# EVK-IRIS-W1-SRAM_RESET_STRAPING.net
KiCad netlist of a schematic drawn in Altium Designer
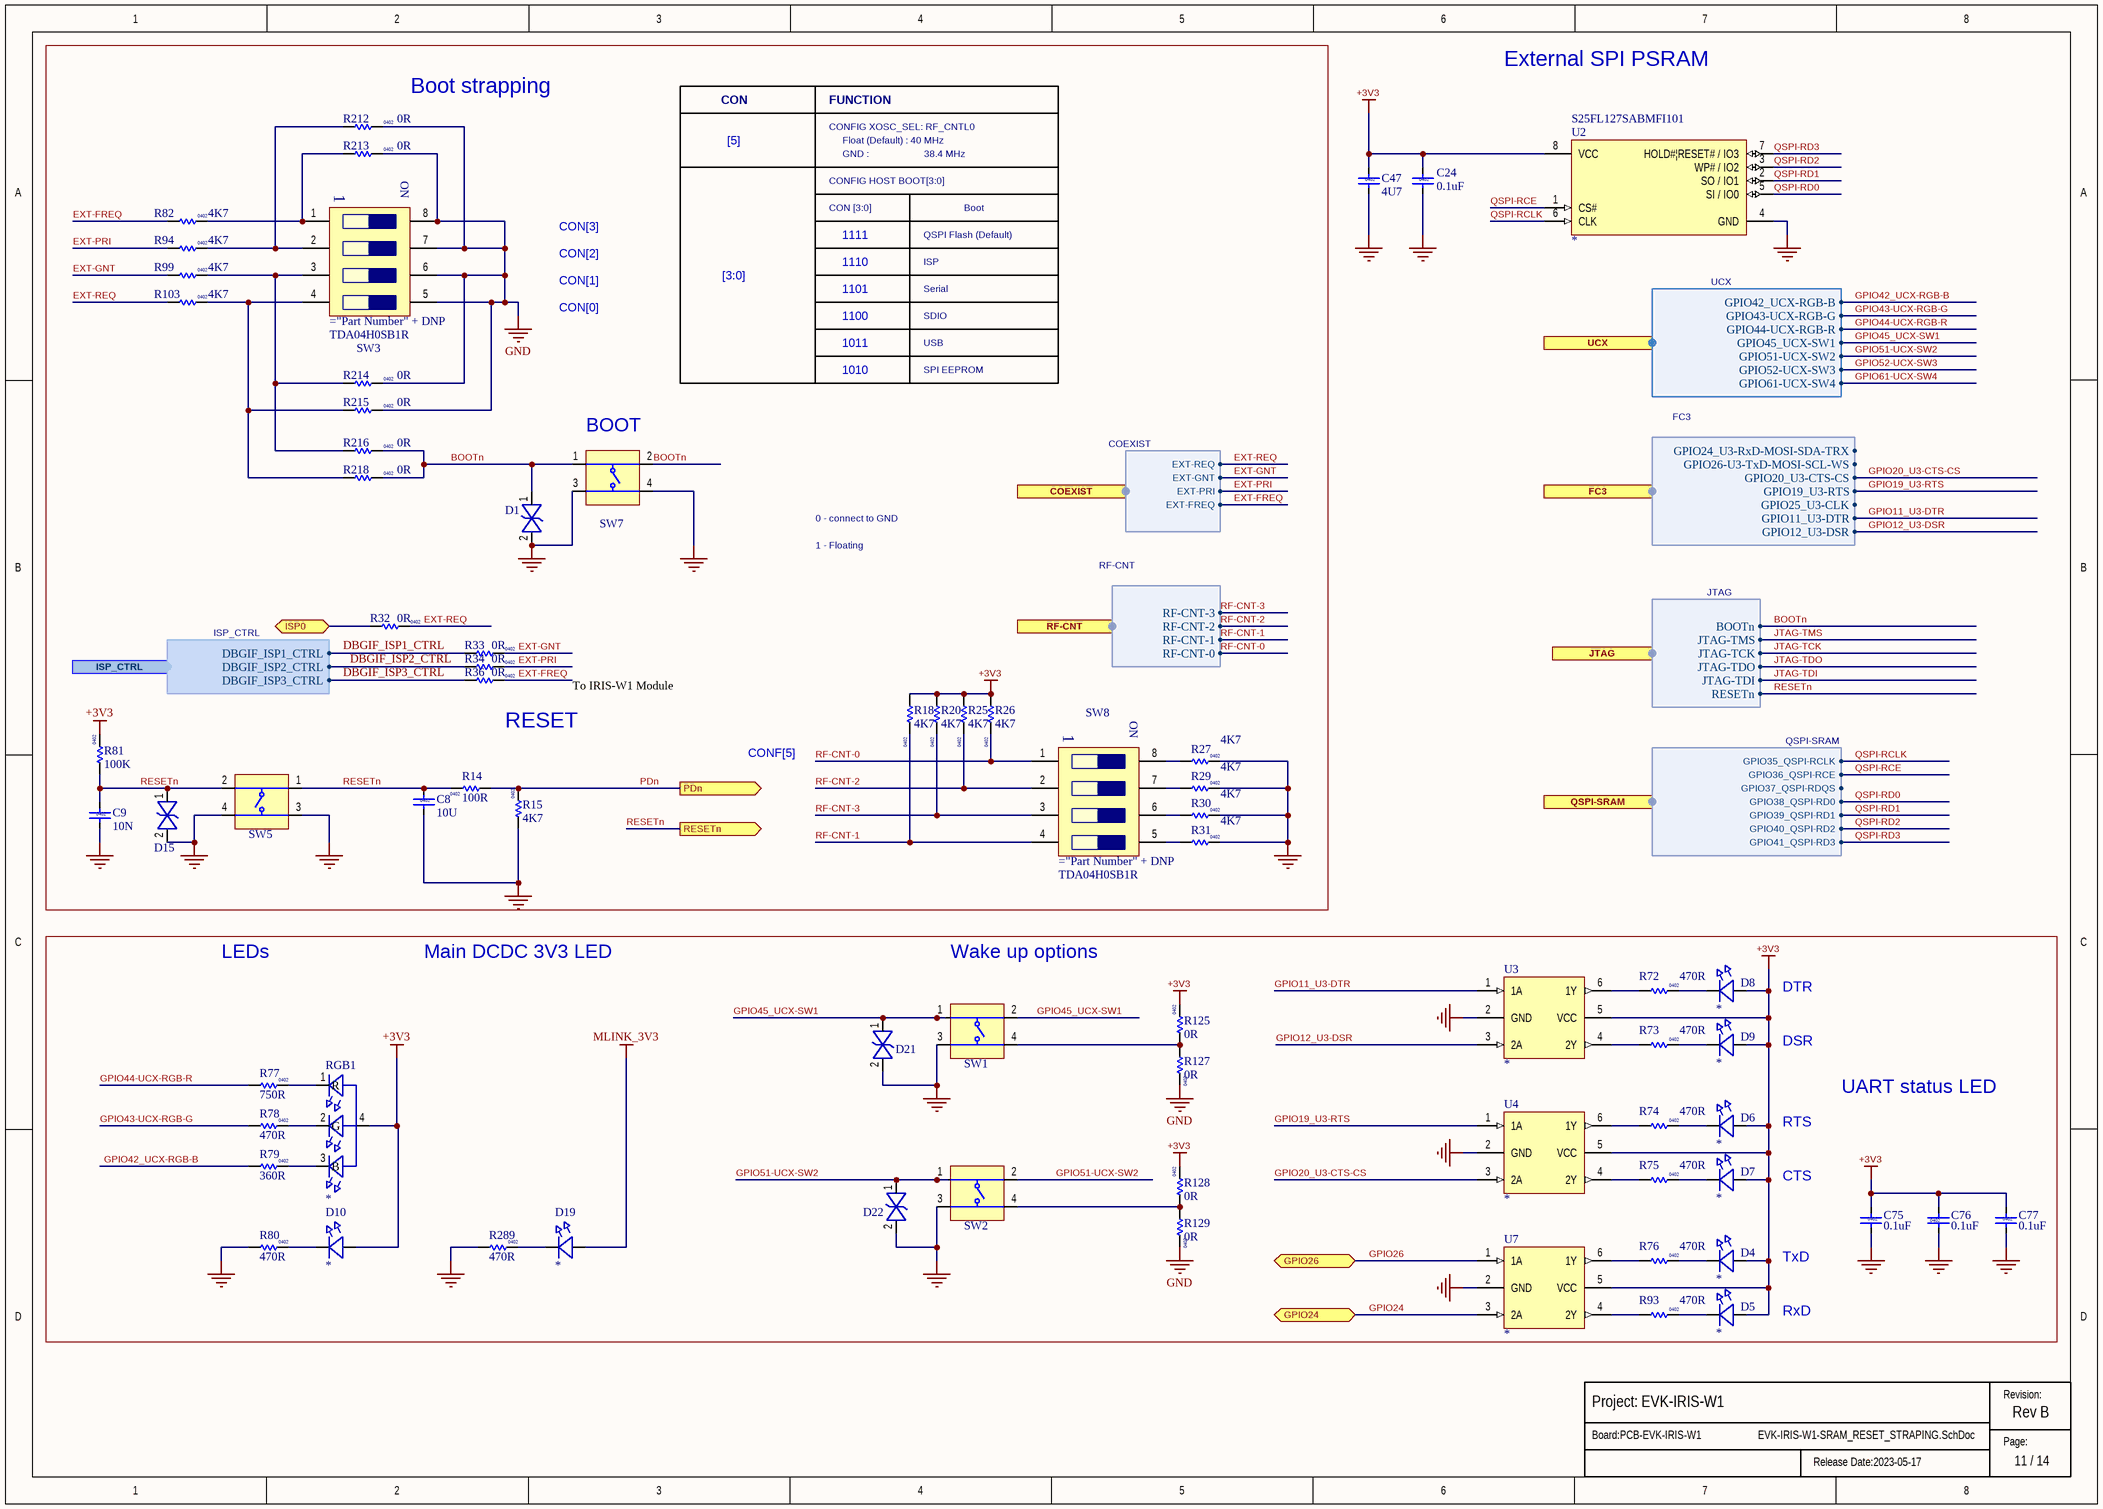
[diagram p0: EVK-IRIS-W1-SRAM_RESET_STRAPING.SchDoc]

(export (version "E")
  (design (tool "Eeschema 10.0.6"))
  (components
    (comp (ref "C8")
      (value "10U")
      (footprint "Cap 0402 HD")
      (description "CAP CER X5R 0402 10U 20% 10V")
      (fields
        (field (name "SIZE") "0402")
        (field (name "PART NUMBER") "UBXH01-0000244")
        (field (name "TOLERANCE") "20%")
        (field (name "EDITOR") "dario.antonaz")
        (field (name "RELEASED BY") "jure.podmenik")
      )
      (libsource (lib "UBX_Parts_DB_Lib") (part "Cap Chip"))
    )
    (comp (ref "C9")
      (value "10N")
      (footprint "Cap 0402")
      (description "CAP CER X7R 0402 10N 10% 16V")
      (fields
        (field (name "SIZE") "0402")
        (field (name "PART NUMBER") "UBXH01-0023025")
        (field (name "TOLERANCE") "10%")
        (field (name "EDITOR") "roland.rust")
        (field (name "RELEASED BY") "anthony.gergis")
      )
      (libsource (lib "UBX_Parts_DB_Lib") (part "Cap Chip"))
    )
    (comp (ref "C24")
      (value "0.1uF")
      (footprint "Cap 0402 HD")
      (description "Cap, Ceramic 0.1uF 10V 10% X5R 0402")
      (fields
        (field (name "SIZE") "0402")
        (field (name "PART NUMBER") "120-00016")
        (field (name "TOLERANCE") "+/- 10%")
      )
      (libsource (lib "Arena_Parts_DB_Lib") (part "Cap Chip"))
    )
    (comp (ref "C47")
      (value "4U7")
      (footprint "Cap 0402 HD")
      (description "CAP CER X5R 0402 4U7 20% 10V")
      (fields
        (field (name "SIZE") "0402")
        (field (name "PART NUMBER") "UBXH01-0000243")
        (field (name "TOLERANCE") "20%")
        (field (name "EDITOR") "martin.pilik")
        (field (name "RELEASED BY") "fabrice.bret-dibat")
      )
      (libsource (lib "UBX_Parts_DB_Lib") (part "Cap Chip"))
    )
    (comp (ref "C75")
      (value "0.1uF")
      (footprint "Cap 0402 HD")
      (description "Cap, Ceramic 0.1uF 10V 10% X5R 0402")
      (fields
        (field (name "SIZE") "0402")
        (field (name "PART NUMBER") "120-00016")
        (field (name "TOLERANCE") "+/- 10%")
      )
      (libsource (lib "Arena_Parts_DB_Lib") (part "Cap Chip"))
    )
    (comp (ref "C76")
      (value "0.1uF")
      (footprint "Cap 0402 HD")
      (description "Cap, Ceramic 0.1uF 10V 10% X5R 0402")
      (fields
        (field (name "SIZE") "0402")
        (field (name "PART NUMBER") "120-00016")
        (field (name "TOLERANCE") "+/- 10%")
      )
      (libsource (lib "Arena_Parts_DB_Lib") (part "Cap Chip"))
    )
    (comp (ref "C77")
      (value "0.1uF")
      (footprint "Cap 0402 HD")
      (description "Cap, Ceramic 0.1uF 10V 10% X5R 0402")
      (fields
        (field (name "SIZE") "0402")
        (field (name "PART NUMBER") "120-00016")
        (field (name "TOLERANCE") "+/- 10%")
      )
      (libsource (lib "Arena_Parts_DB_Lib") (part "Cap Chip"))
    )
    (comp (ref "D1")
      (value "110-00019")
      (footprint "SOD-923")
      (description "Diode, ESD9B, 3.3V, ST5G, SOD-923")
      (fields (field (name "VOLTAGE") "3.3V"))
      (libsource (lib "Arena_Parts_DB_Lib") (part "Diode_TVS"))
    )
    (comp (ref "D4")
      (value "UBXH11-0000018")
      (footprint "LED-0603")
      (description "LED CHIP 0603 LOW CURRENT OSRAM 0.002A GREEN 2.2V 2mA")
      (fields
        (field (name "COLOR") "*")
        (field (name "MANUFACTURER") "Osram")
        (field (name "EDITOR") "johann.furrer")
        (field (name "RELEASED BY") "martin.grasse")
      )
      (libsource (lib "UBX_Parts_DB_Lib") (part "LED_BASE"))
    )
    (comp (ref "D5")
      (value "UBXH11-0000018")
      (footprint "LED-0603")
      (description "LED CHIP 0603 LOW CURRENT OSRAM 0.002A GREEN 2.2V 2mA")
      (fields
        (field (name "COLOR") "*")
        (field (name "MANUFACTURER") "Osram")
        (field (name "EDITOR") "johann.furrer")
        (field (name "RELEASED BY") "martin.grasse")
      )
      (libsource (lib "UBX_Parts_DB_Lib") (part "LED_BASE"))
    )
    (comp (ref "D6")
      (value "UBXH11-0000018")
      (footprint "LED-0603")
      (description "LED CHIP 0603 LOW CURRENT OSRAM 0.002A GREEN 2.2V 2mA")
      (fields
        (field (name "COLOR") "*")
        (field (name "MANUFACTURER") "Osram")
        (field (name "EDITOR") "johann.furrer")
        (field (name "RELEASED BY") "martin.grasse")
      )
      (libsource (lib "UBX_Parts_DB_Lib") (part "LED_BASE"))
    )
    (comp (ref "D7")
      (value "UBXH11-0000018")
      (footprint "LED-0603")
      (description "LED CHIP 0603 LOW CURRENT OSRAM 0.002A GREEN 2.2V 2mA")
      (fields
        (field (name "COLOR") "*")
        (field (name "MANUFACTURER") "Osram")
        (field (name "EDITOR") "johann.furrer")
        (field (name "RELEASED BY") "martin.grasse")
      )
      (libsource (lib "UBX_Parts_DB_Lib") (part "LED_BASE"))
    )
    (comp (ref "D8")
      (value "UBXH11-0000018")
      (footprint "LED-0603")
      (description "LED CHIP 0603 LOW CURRENT OSRAM 0.002A GREEN 2.2V 2mA")
      (fields
        (field (name "COLOR") "*")
        (field (name "MANUFACTURER") "Osram")
        (field (name "EDITOR") "johann.furrer")
        (field (name "RELEASED BY") "martin.grasse")
      )
      (libsource (lib "UBX_Parts_DB_Lib") (part "LED_BASE"))
    )
    (comp (ref "D9")
      (value "UBXH11-0000018")
      (footprint "LED-0603")
      (description "LED CHIP 0603 LOW CURRENT OSRAM 0.002A GREEN 2.2V 2mA")
      (fields
        (field (name "COLOR") "*")
        (field (name "MANUFACTURER") "Osram")
        (field (name "EDITOR") "johann.furrer")
        (field (name "RELEASED BY") "martin.grasse")
      )
      (libsource (lib "UBX_Parts_DB_Lib") (part "LED_BASE"))
    )
    (comp (ref "D10")
      (value "UBXH11-0000018")
      (footprint "LED-0603")
      (description "LED CHIP 0603 LOW CURRENT OSRAM 0.002A GREEN 2.2V 2mA")
      (fields
        (field (name "COLOR") "*")
        (field (name "MANUFACTURER") "Osram")
        (field (name "EDITOR") "johann.furrer")
        (field (name "RELEASED BY") "martin.grasse")
      )
      (libsource (lib "UBX_Parts_DB_Lib") (part "LED_BASE"))
    )
    (comp (ref "D15")
      (value "110-00019")
      (footprint "SOD-923")
      (description "Diode, ESD9B, 3.3V, ST5G, SOD-923")
      (fields (field (name "VOLTAGE") "3.3V"))
      (libsource (lib "Arena_Parts_DB_Lib") (part "Diode_TVS"))
    )
    (comp (ref "D19")
      (value "UBXH11-0000018")
      (footprint "LED-0603")
      (description "LED CHIP 0603 LOW CURRENT OSRAM 0.002A GREEN 2.2V 2mA")
      (fields
        (field (name "COLOR") "*")
        (field (name "MANUFACTURER") "Osram")
        (field (name "EDITOR") "johann.furrer")
        (field (name "RELEASED BY") "martin.grasse")
      )
      (libsource (lib "UBX_Parts_DB_Lib") (part "LED_BASE"))
    )
    (comp (ref "D21")
      (value "110-00019")
      (footprint "SOD-923")
      (description "Diode, ESD9B, 3.3V, ST5G, SOD-923")
      (fields (field (name "VOLTAGE") "3.3V"))
      (libsource (lib "Arena_Parts_DB_Lib") (part "Diode_TVS"))
    )
    (comp (ref "D22")
      (value "110-00019")
      (footprint "SOD-923")
      (description "Diode, ESD9B, 3.3V, ST5G, SOD-923")
      (fields (field (name "VOLTAGE") "3.3V"))
      (libsource (lib "Arena_Parts_DB_Lib") (part "Diode_TVS"))
    )
    (comp (ref "R14")
      (value "100R")
      (footprint "RES 0402 HD")
      (description "RES THIN FILM CHIP 0402 100R 0.1% 100mW")
      (fields
        (field (name "SIZE") "0402")
        (field (name "PART NUMBER") "UBXH18-0000504")
        (field (name "TOLERANCE") "0.1%")
        (field (name "EDITOR") "martin.kessel")
      )
      (libsource (lib "UBX_Parts_DB_Lib") (part "Res sm"))
    )
    (comp (ref "R15")
      (value "4K7")
      (footprint "RES 0402 HD")
      (description "RES THICK FILM CHIP 0402 4K7 1% 63mW")
      (fields
        (field (name "SIZE") "0402")
        (field (name "PART NUMBER") "UBXH18-0000213")
        (field (name "TOLERANCE") "1%")
        (field (name "EDITOR") "michael.hein")
        (field (name "RELEASED BY") "vasyl.dykyy")
      )
      (libsource (lib "UBX_Parts_DB_Lib") (part "Res sm"))
    )
    (comp (ref "R18")
      (value "4K7")
      (footprint "RES 0402 HD")
      (description "RES THICK FILM CHIP 0402 4K7 1% 63mW")
      (fields
        (field (name "SIZE") "0402")
        (field (name "PART NUMBER") "UBXH18-0000213")
        (field (name "TOLERANCE") "1%")
        (field (name "EDITOR") "michael.hein")
        (field (name "RELEASED BY") "vasyl.dykyy")
      )
      (libsource (lib "UBX_Parts_DB_Lib") (part "Res sm"))
    )
    (comp (ref "R20")
      (value "4K7")
      (footprint "RES 0402 HD")
      (description "RES THICK FILM CHIP 0402 4K7 1% 63mW")
      (fields
        (field (name "SIZE") "0402")
        (field (name "PART NUMBER") "UBXH18-0000213")
        (field (name "TOLERANCE") "1%")
        (field (name "EDITOR") "michael.hein")
        (field (name "RELEASED BY") "vasyl.dykyy")
      )
      (libsource (lib "UBX_Parts_DB_Lib") (part "Res sm"))
    )
    (comp (ref "R25")
      (value "4K7")
      (footprint "RES 0402 HD")
      (description "RES THICK FILM CHIP 0402 4K7 1% 63mW")
      (fields
        (field (name "SIZE") "0402")
        (field (name "PART NUMBER") "UBXH18-0000213")
        (field (name "TOLERANCE") "1%")
        (field (name "EDITOR") "michael.hein")
        (field (name "RELEASED BY") "vasyl.dykyy")
      )
      (libsource (lib "UBX_Parts_DB_Lib") (part "Res sm"))
    )
    (comp (ref "R26")
      (value "4K7")
      (footprint "RES 0402 HD")
      (description "RES THICK FILM CHIP 0402 4K7 1% 63mW")
      (fields
        (field (name "SIZE") "0402")
        (field (name "PART NUMBER") "UBXH18-0000213")
        (field (name "TOLERANCE") "1%")
        (field (name "EDITOR") "michael.hein")
        (field (name "RELEASED BY") "vasyl.dykyy")
      )
      (libsource (lib "UBX_Parts_DB_Lib") (part "Res sm"))
    )
    (comp (ref "R27")
      (value "4K7")
      (footprint "RES 0402 HD")
      (description "RES THICK FILM CHIP 0402 4K7 1% 63mW")
      (fields
        (field (name "SIZE") "0402")
        (field (name "PART NUMBER") "UBXH18-0000213")
        (field (name "TOLERANCE") "1%")
        (field (name "EDITOR") "michael.hein")
        (field (name "RELEASED BY") "vasyl.dykyy")
      )
      (libsource (lib "UBX_Parts_DB_Lib") (part "Res sm"))
    )
    (comp (ref "R29")
      (value "4K7")
      (footprint "RES 0402 HD")
      (description "RES THICK FILM CHIP 0402 4K7 1% 63mW")
      (fields
        (field (name "SIZE") "0402")
        (field (name "PART NUMBER") "UBXH18-0000213")
        (field (name "TOLERANCE") "1%")
        (field (name "EDITOR") "michael.hein")
        (field (name "RELEASED BY") "vasyl.dykyy")
      )
      (libsource (lib "UBX_Parts_DB_Lib") (part "Res sm"))
    )
    (comp (ref "R30")
      (value "4K7")
      (footprint "RES 0402 HD")
      (description "RES THICK FILM CHIP 0402 4K7 1% 63mW")
      (fields
        (field (name "SIZE") "0402")
        (field (name "PART NUMBER") "UBXH18-0000213")
        (field (name "TOLERANCE") "1%")
        (field (name "EDITOR") "michael.hein")
        (field (name "RELEASED BY") "vasyl.dykyy")
      )
      (libsource (lib "UBX_Parts_DB_Lib") (part "Res sm"))
    )
    (comp (ref "R31")
      (value "4K7")
      (footprint "RES 0402 HD")
      (description "RES THICK FILM CHIP 0402 4K7 1% 63mW")
      (fields
        (field (name "SIZE") "0402")
        (field (name "PART NUMBER") "UBXH18-0000213")
        (field (name "TOLERANCE") "1%")
        (field (name "EDITOR") "michael.hein")
        (field (name "RELEASED BY") "vasyl.dykyy")
      )
      (libsource (lib "UBX_Parts_DB_Lib") (part "Res sm"))
    )
    (comp (ref "R32")
      (value "0R")
      (footprint "RES 0402 HD")
      (description "RES THICK FILM CHIP 0402 0R 0 100mW")
      (fields
        (field (name "SIZE") "0402")
        (field (name "PART NUMBER") "UBXH18-0003002")
        (field (name "TOLERANCE") "0")
        (field (name "EDITOR") "charlotte.biber")
        (field (name "RELEASED BY") "peter.mueller")
      )
      (libsource (lib "UBX_Parts_DB_Lib") (part "Res sm"))
    )
    (comp (ref "R33")
      (value "0R")
      (footprint "RES 0402 HD")
      (description "RES THICK FILM CHIP 0402 0R 0 100mW")
      (fields
        (field (name "SIZE") "0402")
        (field (name "PART NUMBER") "UBXH18-0003002")
        (field (name "TOLERANCE") "0")
        (field (name "EDITOR") "charlotte.biber")
        (field (name "RELEASED BY") "peter.mueller")
      )
      (libsource (lib "UBX_Parts_DB_Lib") (part "Res sm"))
    )
    (comp (ref "R34")
      (value "0R")
      (footprint "RES 0402 HD")
      (description "RES THICK FILM CHIP 0402 0R 0 100mW")
      (fields
        (field (name "SIZE") "0402")
        (field (name "PART NUMBER") "UBXH18-0003002")
        (field (name "TOLERANCE") "0")
        (field (name "EDITOR") "charlotte.biber")
        (field (name "RELEASED BY") "peter.mueller")
      )
      (libsource (lib "UBX_Parts_DB_Lib") (part "Res sm"))
    )
    (comp (ref "R36")
      (value "0R")
      (footprint "RES 0402 HD")
      (description "RES THICK FILM CHIP 0402 0R 0 100mW")
      (fields
        (field (name "SIZE") "0402")
        (field (name "PART NUMBER") "UBXH18-0003002")
        (field (name "TOLERANCE") "0")
        (field (name "EDITOR") "charlotte.biber")
        (field (name "RELEASED BY") "peter.mueller")
      )
      (libsource (lib "UBX_Parts_DB_Lib") (part "Res sm"))
    )
    (comp (ref "R72")
      (value "470R")
      (footprint "RES 0402 HD")
      (description "RES THICK FILM CHIP 0402 470R 5% 100mW")
      (fields
        (field (name "SIZE") "0402")
        (field (name "PART NUMBER") "UBXH18-0008041")
        (field (name "TOLERANCE") "5%")
        (field (name "EDITOR") "roland.rust")
        (field (name "RELEASED BY") "roland.rust")
      )
      (libsource (lib "UBX_Parts_DB_Lib") (part "Res sm"))
    )
    (comp (ref "R73")
      (value "470R")
      (footprint "RES 0402 HD")
      (description "RES THICK FILM CHIP 0402 470R 5% 100mW")
      (fields
        (field (name "SIZE") "0402")
        (field (name "PART NUMBER") "UBXH18-0008041")
        (field (name "TOLERANCE") "5%")
        (field (name "EDITOR") "roland.rust")
        (field (name "RELEASED BY") "roland.rust")
      )
      (libsource (lib "UBX_Parts_DB_Lib") (part "Res sm"))
    )
    (comp (ref "R74")
      (value "470R")
      (footprint "RES 0402 HD")
      (description "RES THICK FILM CHIP 0402 470R 5% 100mW")
      (fields
        (field (name "SIZE") "0402")
        (field (name "PART NUMBER") "UBXH18-0008041")
        (field (name "TOLERANCE") "5%")
        (field (name "EDITOR") "roland.rust")
        (field (name "RELEASED BY") "roland.rust")
      )
      (libsource (lib "UBX_Parts_DB_Lib") (part "Res sm"))
    )
    (comp (ref "R75")
      (value "470R")
      (footprint "RES 0402 HD")
      (description "RES THICK FILM CHIP 0402 470R 5% 100mW")
      (fields
        (field (name "SIZE") "0402")
        (field (name "PART NUMBER") "UBXH18-0008041")
        (field (name "TOLERANCE") "5%")
        (field (name "EDITOR") "roland.rust")
        (field (name "RELEASED BY") "roland.rust")
      )
      (libsource (lib "UBX_Parts_DB_Lib") (part "Res sm"))
    )
    (comp (ref "R76")
      (value "470R")
      (footprint "RES 0402 HD")
      (description "RES THICK FILM CHIP 0402 470R 5% 100mW")
      (fields
        (field (name "SIZE") "0402")
        (field (name "PART NUMBER") "UBXH18-0008041")
        (field (name "TOLERANCE") "5%")
        (field (name "EDITOR") "roland.rust")
        (field (name "RELEASED BY") "roland.rust")
      )
      (libsource (lib "UBX_Parts_DB_Lib") (part "Res sm"))
    )
    (comp (ref "R77")
      (value "750R")
      (footprint "RES 0402 HD")
      (description "RES THICK FILM CHIP 0402 750R 5% 100mW")
      (fields
        (field (name "SIZE") "0402")
        (field (name "PART NUMBER") "UBXH18-0008046")
        (field (name "TOLERANCE") "5%")
        (field (name "EDITOR") "jaka.bevk")
        (field (name "RELEASED BY") "erian.bezhani")
      )
      (libsource (lib "UBX_Parts_DB_Lib") (part "Res sm"))
    )
    (comp (ref "R78")
      (value "470R")
      (footprint "RES 0402 HD")
      (description "RES THICK FILM CHIP 0402 470R 5% 100mW")
      (fields
        (field (name "SIZE") "0402")
        (field (name "PART NUMBER") "UBXH18-0008041")
        (field (name "TOLERANCE") "5%")
        (field (name "EDITOR") "roland.rust")
        (field (name "RELEASED BY") "roland.rust")
      )
      (libsource (lib "UBX_Parts_DB_Lib") (part "Res sm"))
    )
    (comp (ref "R79")
      (value "360R")
      (footprint "RES 0402 HD")
      (description "RES THICK FILM CHIP 0402 360R 1% 63mW")
      (fields
        (field (name "SIZE") "0402")
        (field (name "PART NUMBER") "UBXH18-0000216")
        (field (name "TOLERANCE") "1%")
        (field (name "EDITOR") "michael.hein")
        (field (name "RELEASED BY") "vasyl.dykyy")
      )
      (libsource (lib "UBX_Parts_DB_Lib") (part "Res sm"))
    )
    (comp (ref "R80")
      (value "470R")
      (footprint "RES 0402 HD")
      (description "RES THICK FILM CHIP 0402 470R 5% 100mW")
      (fields
        (field (name "SIZE") "0402")
        (field (name "PART NUMBER") "UBXH18-0008041")
        (field (name "TOLERANCE") "5%")
        (field (name "EDITOR") "roland.rust")
        (field (name "RELEASED BY") "roland.rust")
      )
      (libsource (lib "UBX_Parts_DB_Lib") (part "Res sm"))
    )
    (comp (ref "R81")
      (value "100K")
      (footprint "RES 0402 HD")
      (description "RES THICK FILM CHIP 0402 100K 5% 100mW")
      (fields
        (field (name "SIZE") "0402")
        (field (name "PART NUMBER") "UBXH18-0008097")
        (field (name "TOLERANCE") "5%")
        (field (name "EDITOR") "roland.rust")
        (field (name "RELEASED BY") "roland.rust")
      )
      (libsource (lib "UBX_Parts_DB_Lib") (part "Res sm"))
    )
    (comp (ref "R82")
      (value "4K7")
      (footprint "RES 0402 HD")
      (description "RES THICK FILM CHIP 0402 4K7 1% 63mW")
      (fields
        (field (name "SIZE") "0402")
        (field (name "PART NUMBER") "UBXH18-0000213")
        (field (name "TOLERANCE") "1%")
        (field (name "EDITOR") "michael.hein")
        (field (name "RELEASED BY") "vasyl.dykyy")
      )
      (libsource (lib "UBX_Parts_DB_Lib") (part "Res sm"))
    )
    (comp (ref "R93")
      (value "470R")
      (footprint "RES 0402 HD")
      (description "RES THICK FILM CHIP 0402 470R 5% 100mW")
      (fields
        (field (name "SIZE") "0402")
        (field (name "PART NUMBER") "UBXH18-0008041")
        (field (name "TOLERANCE") "5%")
        (field (name "EDITOR") "roland.rust")
        (field (name "RELEASED BY") "roland.rust")
      )
      (libsource (lib "UBX_Parts_DB_Lib") (part "Res sm"))
    )
    (comp (ref "R94")
      (value "4K7")
      (footprint "RES 0402 HD")
      (description "RES THICK FILM CHIP 0402 4K7 1% 63mW")
      (fields
        (field (name "SIZE") "0402")
        (field (name "PART NUMBER") "UBXH18-0000213")
        (field (name "TOLERANCE") "1%")
        (field (name "EDITOR") "michael.hein")
        (field (name "RELEASED BY") "vasyl.dykyy")
      )
      (libsource (lib "UBX_Parts_DB_Lib") (part "Res sm"))
    )
    (comp (ref "R99")
      (value "4K7")
      (footprint "RES 0402 HD")
      (description "RES THICK FILM CHIP 0402 4K7 1% 63mW")
      (fields
        (field (name "SIZE") "0402")
        (field (name "PART NUMBER") "UBXH18-0000213")
        (field (name "TOLERANCE") "1%")
        (field (name "EDITOR") "michael.hein")
        (field (name "RELEASED BY") "vasyl.dykyy")
      )
      (libsource (lib "UBX_Parts_DB_Lib") (part "Res sm"))
    )
    (comp (ref "R103")
      (value "4K7")
      (footprint "RES 0402 HD")
      (description "RES THICK FILM CHIP 0402 4K7 1% 63mW")
      (fields
        (field (name "SIZE") "0402")
        (field (name "PART NUMBER") "UBXH18-0000213")
        (field (name "TOLERANCE") "1%")
        (field (name "EDITOR") "michael.hein")
        (field (name "RELEASED BY") "vasyl.dykyy")
      )
      (libsource (lib "UBX_Parts_DB_Lib") (part "Res sm"))
    )
    (comp (ref "R125")
      (value "0R")
      (footprint "RES 0402 HD")
      (description "RES THICK FILM CHIP 0402 0R 0 100mW")
      (fields
        (field (name "SIZE") "0402")
        (field (name "PART NUMBER") "UBXH18-0003002")
        (field (name "TOLERANCE") "0")
        (field (name "EDITOR") "charlotte.biber")
        (field (name "RELEASED BY") "peter.mueller")
      )
      (libsource (lib "UBX_Parts_DB_Lib") (part "Res sm"))
    )
    (comp (ref "R127")
      (value "0R")
      (footprint "RES 0402 HD")
      (description "RES THICK FILM CHIP 0402 0R 0 100mW")
      (fields
        (field (name "SIZE") "0402")
        (field (name "PART NUMBER") "UBXH18-0003002")
        (field (name "TOLERANCE") "0")
        (field (name "EDITOR") "charlotte.biber")
        (field (name "RELEASED BY") "peter.mueller")
      )
      (libsource (lib "UBX_Parts_DB_Lib") (part "Res sm"))
    )
    (comp (ref "R128")
      (value "0R")
      (footprint "RES 0402 HD")
      (description "RES THICK FILM CHIP 0402 0R 0 100mW")
      (fields
        (field (name "SIZE") "0402")
        (field (name "PART NUMBER") "UBXH18-0003002")
        (field (name "TOLERANCE") "0")
        (field (name "EDITOR") "charlotte.biber")
        (field (name "RELEASED BY") "peter.mueller")
      )
      (libsource (lib "UBX_Parts_DB_Lib") (part "Res sm"))
    )
    (comp (ref "R129")
      (value "0R")
      (footprint "RES 0402 HD")
      (description "RES THICK FILM CHIP 0402 0R 0 100mW")
      (fields
        (field (name "SIZE") "0402")
        (field (name "PART NUMBER") "UBXH18-0003002")
        (field (name "TOLERANCE") "0")
        (field (name "EDITOR") "charlotte.biber")
        (field (name "RELEASED BY") "peter.mueller")
      )
      (libsource (lib "UBX_Parts_DB_Lib") (part "Res sm"))
    )
    (comp (ref "R212")
      (value "0R")
      (footprint "RES 0402 HD")
      (description "RES THICK FILM CHIP 0402 0R 0 100mW")
      (fields
        (field (name "SIZE") "0402")
        (field (name "PART NUMBER") "UBXH18-0003002")
        (field (name "TOLERANCE") "0")
        (field (name "EDITOR") "charlotte.biber")
        (field (name "RELEASED BY") "peter.mueller")
      )
      (libsource (lib "UBX_Parts_DB_Lib") (part "Res sm"))
    )
    (comp (ref "R213")
      (value "0R")
      (footprint "RES 0402 HD")
      (description "RES THICK FILM CHIP 0402 0R 0 100mW")
      (fields
        (field (name "SIZE") "0402")
        (field (name "PART NUMBER") "UBXH18-0003002")
        (field (name "TOLERANCE") "0")
        (field (name "EDITOR") "charlotte.biber")
        (field (name "RELEASED BY") "peter.mueller")
      )
      (libsource (lib "UBX_Parts_DB_Lib") (part "Res sm"))
    )
    (comp (ref "R214")
      (value "0R")
      (footprint "RES 0402 HD")
      (description "RES THICK FILM CHIP 0402 0R 0 100mW")
      (fields
        (field (name "SIZE") "0402")
        (field (name "PART NUMBER") "UBXH18-0003002")
        (field (name "TOLERANCE") "0")
        (field (name "EDITOR") "charlotte.biber")
        (field (name "RELEASED BY") "peter.mueller")
      )
      (libsource (lib "UBX_Parts_DB_Lib") (part "Res sm"))
    )
    (comp (ref "R215")
      (value "0R")
      (footprint "RES 0402 HD")
      (description "RES THICK FILM CHIP 0402 0R 0 100mW")
      (fields
        (field (name "SIZE") "0402")
        (field (name "PART NUMBER") "UBXH18-0003002")
        (field (name "TOLERANCE") "0")
        (field (name "EDITOR") "charlotte.biber")
        (field (name "RELEASED BY") "peter.mueller")
      )
      (libsource (lib "UBX_Parts_DB_Lib") (part "Res sm"))
    )
    (comp (ref "R216")
      (value "0R")
      (footprint "RES 0402 HD")
      (description "RES THICK FILM CHIP 0402 0R 0 100mW")
      (fields
        (field (name "SIZE") "0402")
        (field (name "PART NUMBER") "UBXH18-0003002")
        (field (name "TOLERANCE") "0")
        (field (name "EDITOR") "charlotte.biber")
        (field (name "RELEASED BY") "peter.mueller")
      )
      (libsource (lib "UBX_Parts_DB_Lib") (part "Res sm"))
    )
    (comp (ref "R218")
      (value "0R")
      (footprint "RES 0402 HD")
      (description "RES THICK FILM CHIP 0402 0R 0 100mW")
      (fields
        (field (name "SIZE") "0402")
        (field (name "PART NUMBER") "UBXH18-0003002")
        (field (name "TOLERANCE") "0")
        (field (name "EDITOR") "charlotte.biber")
        (field (name "RELEASED BY") "peter.mueller")
      )
      (libsource (lib "UBX_Parts_DB_Lib") (part "Res sm"))
    )
    (comp (ref "R289")
      (value "470R")
      (footprint "RES 0402 HD")
      (description "RES THICK FILM CHIP 0402 470R 5% 100mW")
      (fields
        (field (name "SIZE") "0402")
        (field (name "PART NUMBER") "UBXH18-0008041")
        (field (name "TOLERANCE") "5%")
        (field (name "EDITOR") "roland.rust")
        (field (name "RELEASED BY") "roland.rust")
      )
      (libsource (lib "UBX_Parts_DB_Lib") (part "Res sm"))
    )
    (comp (ref "RGB1")
      (value "115-00026")
      (footprint "LED_1616")
      (description "LED RGB SMT 0606")
      (fields (field (name "COLOR") "*") (field (name "VOLTAGE") "None"))
      (libsource (lib "Arena_Parts_DB_Lib") (part "LED_RGB_CA_4"))
    )
    (comp (ref "SW1")
      (value "135-00002")
      (footprint "SW_TACT_SMT_6mm")
      (description "Tactile Switch, SPST-NO, SMT, Actuation force = 160g, 6mm x 6mm")
      (fields (field (name "VOLTAGE") "12VDC"))
      (libsource (lib "Arena_Parts_DB_Lib") (part "SW_TACT_SPST_4Pin"))
    )
    (comp (ref "SW2")
      (value "135-00002")
      (footprint "SW_TACT_SMT_6mm")
      (description "Tactile Switch, SPST-NO, SMT, Actuation force = 160g, 6mm x 6mm")
      (fields (field (name "VOLTAGE") "12VDC"))
      (libsource (lib "Arena_Parts_DB_Lib") (part "SW_TACT_SPST_4Pin"))
    )
    (comp (ref "SW3")
      (value "137-00012")
      (footprint "SOP1.27P6.2x6.2-8Pin")
      (description "Dip Switch SPST 4 Position Surface Mount Slide (Standard) Actuator 25mA 24VDC")
      (fields (field (name "VOLTAGE") "24V") (field (name "MANUFACTURER PART NUMBER 1") "TDA04H0SB1R"))
      (libsource (lib "Arena_Parts_DB_Lib") (part "TDA04H0SB1R"))
    )
    (comp (ref "SW5")
      (value "135-00002")
      (footprint "SW_TACT_SMT_6mm")
      (description "Tactile Switch, SPST-NO, SMT, Actuation force = 160g, 6mm x 6mm")
      (fields (field (name "VOLTAGE") "12VDC"))
      (libsource (lib "") (part "SW_TACT_SPST_4Pin_1"))
    )
    (comp (ref "SW7")
      (value "135-00002")
      (footprint "SW_TACT_SMT_6mm")
      (description "Tactile Switch, SPST-NO, SMT, Actuation force = 160g, 6mm x 6mm")
      (fields (field (name "VOLTAGE") "12VDC"))
      (libsource (lib "Arena_Parts_DB_Lib") (part "SW_TACT_SPST_4Pin"))
    )
    (comp (ref "SW8")
      (value "137-00012")
      (footprint "SOP1.27P6.2x6.2-8Pin")
      (description "Dip Switch SPST 4 Position Surface Mount Slide (Standard) Actuator 25mA 24VDC")
      (fields (field (name "VOLTAGE") "24V") (field (name "MANUFACTURER PART NUMBER 1") "TDA04H0SB1R"))
      (libsource (lib "Arena_Parts_DB_Lib") (part "TDA04H0SB1R"))
    )
    (comp (ref "U2")
      (value "240-00017")
      (footprint "SOIC-8W")
      (description "IC, Flash 128MBIT, 108MHz, 8SOIC")
      (fields
        (field (name "MANUFACTURER P/N") "*")
        (field (name "MANUFACTURER PART NUMBER 1") "S25FL127SABMFI101")
        (field (name "VOLTAGE") "3.6V")
      )
      (libsource (lib "Arena_Parts_DB_Lib") (part "SPI_Flash_Memory_8Pin"))
    )
    (comp (ref "U3")
      (value "225-00022")
      (footprint "SC70-6")
      (description "Buffer, Non-Inverting 2 Element 1 Bit per Element Push-Pull Output SC-70-6")
      (fields (field (name "MANUFACTURER P/N") "*") (field (name "VOLTAGE") "5.5V"))
      (libsource (lib "Arena_Parts_DB_Lib") (part "Buffer_2bit"))
    )
    (comp (ref "U4")
      (value "225-00022")
      (footprint "SC70-6")
      (description "Buffer, Non-Inverting 2 Element 1 Bit per Element Push-Pull Output SC-70-6")
      (fields (field (name "MANUFACTURER P/N") "*") (field (name "VOLTAGE") "5.5V"))
      (libsource (lib "Arena_Parts_DB_Lib") (part "Buffer_2bit"))
    )
    (comp (ref "U7")
      (value "225-00022")
      (footprint "SC70-6")
      (description "Buffer, Non-Inverting 2 Element 1 Bit per Element Push-Pull Output SC-70-6")
      (fields (field (name "MANUFACTURER P/N") "*") (field (name "VOLTAGE") "5.5V"))
      (libsource (lib "Arena_Parts_DB_Lib") (part "Buffer_2bit"))
    )
  )
  (nets
    (net (code "8") (name "+3V3") (class "Default")
      (node (ref "C24") (pin "1") (pinfunction "1_1") (pintype "passive"))
      (node (ref "C47") (pin "1") (pinfunction "1_1") (pintype "passive"))
      (node (ref "C75") (pin "1") (pinfunction "1_1") (pintype "passive"))
      (node (ref "C76") (pin "1") (pinfunction "1_1") (pintype "passive"))
      (node (ref "C77") (pin "1") (pinfunction "1_1") (pintype "passive"))
      (node (ref "D10") (pin "2") (pinfunction "A_2") (pintype "passive"))
      (node (ref "D4") (pin "2") (pinfunction "A_2") (pintype "passive"))
      (node (ref "D5") (pin "2") (pinfunction "A_2") (pintype "passive"))
      (node (ref "D6") (pin "2") (pinfunction "A_2") (pintype "passive"))
      (node (ref "D7") (pin "2") (pinfunction "A_2") (pintype "passive"))
      (node (ref "D8") (pin "2") (pinfunction "A_2") (pintype "passive"))
      (node (ref "D9") (pin "2") (pinfunction "A_2") (pintype "passive"))
      (node (ref "R125") (pin "2") (pinfunction "2_2") (pintype "passive"))
      (node (ref "R128") (pin "2") (pinfunction "2_2") (pintype "passive"))
      (node (ref "R18") (pin "2") (pinfunction "2_2") (pintype "passive"))
      (node (ref "R20") (pin "2") (pinfunction "2_2") (pintype "passive"))
      (node (ref "R25") (pin "2") (pinfunction "2_2") (pintype "passive"))
      (node (ref "R26") (pin "2") (pinfunction "2_2") (pintype "passive"))
      (node (ref "R81") (pin "2") (pinfunction "2_2") (pintype "passive"))
      (node (ref "RGB1") (pin "4") (pinfunction "A_4") (pintype "passive"))
      (node (ref "U2") (pin "8") (pinfunction "VCC_8") (pintype "power_in"))
      (node (ref "U3") (pin "5") (pinfunction "VCC_5") (pintype "power_in"))
      (node (ref "U4") (pin "5") (pinfunction "VCC_5") (pintype "power_in"))
      (node (ref "U7") (pin "5") (pinfunction "VCC_5") (pintype "power_in"))
    )
    (net (code "9") (name "/BOOTn") (class "Default")
      (node (ref "D1") (pin "1") (pintype "passive"))
      (node (ref "R216") (pin "2") (pinfunction "2_2") (pintype "passive"))
      (node (ref "R218") (pin "2") (pinfunction "2_2") (pintype "passive"))
      (node (ref "SW7") (pin "1") (pinfunction "T1_1") (pintype "passive"))
      (node (ref "SW7") (pin "2") (pinfunction "T2_2") (pintype "passive"))
    )
    (net (code "10") (name "/DBGIF_ISP1_CTRL") (class "Default")
      (node (ref "R33") (pin "1") (pinfunction "1_1") (pintype "passive"))
    )
    (net (code "11") (name "/DBGIF_ISP2_CTRL") (class "Default")
      (node (ref "R34") (pin "1") (pinfunction "1_1") (pintype "passive"))
    )
    (net (code "12") (name "/DBGIF_ISP3_CTRL") (class "Default")
      (node (ref "R36") (pin "1") (pinfunction "1_1") (pintype "passive"))
    )
    (net (code "13") (name "/EXT-FREQ") (class "Default")
      (node (ref "R36") (pin "2") (pinfunction "2_2") (pintype "passive"))
      (node (ref "R82") (pin "1") (pinfunction "1_1") (pintype "passive"))
    )
    (net (code "14") (name "/EXT-GNT") (class "Default")
      (node (ref "R33") (pin "2") (pinfunction "2_2") (pintype "passive"))
      (node (ref "R99") (pin "1") (pinfunction "1_1") (pintype "passive"))
    )
    (net (code "15") (name "/EXT-PRI") (class "Default")
      (node (ref "R34") (pin "2") (pinfunction "2_2") (pintype "passive"))
      (node (ref "R94") (pin "1") (pinfunction "1_1") (pintype "passive"))
    )
    (net (code "16") (name "/EXT-REQ") (class "Default")
      (node (ref "R103") (pin "1") (pinfunction "1_1") (pintype "passive"))
      (node (ref "R32") (pin "2") (pinfunction "2_2") (pintype "passive"))
    )
    (net (code "17") (name "/GPIO11_U3-DTR") (class "Default")
      (node (ref "U3") (pin "1") (pinfunction "1A_1") (pintype "input"))
    )
    (net (code "18") (name "/GPIO12_U3-DSR") (class "Default")
      (node (ref "U3") (pin "3") (pinfunction "2A_3") (pintype "input"))
    )
    (net (code "19") (name "/GPIO19_U3-RTS") (class "Default")
      (node (ref "U4") (pin "1") (pinfunction "1A_1") (pintype "input"))
    )
    (net (code "20") (name "/GPIO20_U3-CTS-CS") (class "Default")
      (node (ref "U4") (pin "3") (pinfunction "2A_3") (pintype "input"))
    )
    (net (code "21") (name "/GPIO24") (class "Default")
      (node (ref "U7") (pin "3") (pinfunction "2A_3") (pintype "input"))
    )
    (net (code "22") (name "/GPIO26") (class "Default")
      (node (ref "U7") (pin "1") (pinfunction "1A_1") (pintype "input"))
    )
    (net (code "23") (name "/GPIO42_UCX-RGB-B") (class "Default")
      (node (ref "R79") (pin "1") (pinfunction "1_1") (pintype "passive"))
    )
    (net (code "24") (name "/GPIO43-UCX-RGB-G") (class "Default")
      (node (ref "R78") (pin "1") (pinfunction "1_1") (pintype "passive"))
    )
    (net (code "25") (name "/GPIO44-UCX-RGB-R") (class "Default")
      (node (ref "R77") (pin "1") (pinfunction "1_1") (pintype "passive"))
    )
    (net (code "26") (name "/GPIO45_UCX-SW1") (class "Default")
      (node (ref "D21") (pin "1") (pintype "passive"))
      (node (ref "SW1") (pin "1") (pinfunction "T1_1") (pintype "passive"))
      (node (ref "SW1") (pin "2") (pinfunction "T2_2") (pintype "passive"))
    )
    (net (code "27") (name "/GPIO51-UCX-SW2") (class "Default")
      (node (ref "D22") (pin "1") (pintype "passive"))
      (node (ref "SW2") (pin "1") (pinfunction "T1_1") (pintype "passive"))
      (node (ref "SW2") (pin "2") (pinfunction "T2_2") (pintype "passive"))
    )
    (net (code "30") (name "/ISP0") (class "Default")
      (node (ref "R32") (pin "1") (pinfunction "1_1") (pintype "passive"))
    )
    (net (code "35") (name "/PDn") (class "Default")
      (node (ref "R14") (pin "1") (pinfunction "1_1") (pintype "passive"))
      (node (ref "R15") (pin "2") (pinfunction "2_2") (pintype "passive"))
    )
    (net (code "36") (name "/QSPI-RCE") (class "Default")
      (node (ref "U2") (pin "1") (pinfunction "CS#_1") (pintype "input"))
    )
    (net (code "37") (name "/QSPI-RCLK") (class "Default")
      (node (ref "U2") (pin "6") (pinfunction "CLK_6") (pintype "input"))
    )
    (net (code "38") (name "/QSPI-RD0") (class "Default")
      (node (ref "U2") (pin "5") (pinfunction "SI_/_IO0_5") (pintype "bidirectional"))
    )
    (net (code "39") (name "/QSPI-RD1") (class "Default")
      (node (ref "U2") (pin "2") (pinfunction "SO_/_IO1_2") (pintype "bidirectional"))
    )
    (net (code "40") (name "/QSPI-RD2") (class "Default")
      (node (ref "U2") (pin "3") (pinfunction "WP#_/_IO2_3") (pintype "bidirectional"))
    )
    (net (code "41") (name "/QSPI-RD3") (class "Default")
      (node (ref "U2") (pin "7") (pinfunction "HOLD#¦RESET#_/_IO3_7") (pintype "bidirectional"))
    )
    (net (code "42") (name "/RESETn") (class "Default")
      (node (ref "C8") (pin "1") (pinfunction "1_1") (pintype "passive"))
      (node (ref "C9") (pin "1") (pinfunction "1_1") (pintype "passive"))
      (node (ref "D15") (pin "1") (pintype "passive"))
      (node (ref "R14") (pin "2") (pinfunction "2_2") (pintype "passive"))
      (node (ref "R81") (pin "1") (pinfunction "1_1") (pintype "passive"))
      (node (ref "SW5") (pin "1") (pinfunction "T1_1") (pintype "passive"))
      (node (ref "SW5") (pin "2") (pinfunction "T2_2") (pintype "passive"))
    )
    (net (code "43") (name "/RF-CNT-0") (class "Default")
      (node (ref "R26") (pin "1") (pinfunction "1_1") (pintype "passive"))
      (node (ref "SW8") (pin "1") (pintype "passive"))
    )
    (net (code "44") (name "/RF-CNT-1") (class "Default")
      (node (ref "R18") (pin "1") (pinfunction "1_1") (pintype "passive"))
      (node (ref "SW8") (pin "4") (pintype "passive"))
    )
    (net (code "45") (name "/RF-CNT-2") (class "Default")
      (node (ref "R25") (pin "1") (pinfunction "1_1") (pintype "passive"))
      (node (ref "SW8") (pin "2") (pintype "passive"))
    )
    (net (code "46") (name "/RF-CNT-3") (class "Default")
      (node (ref "R20") (pin "1") (pinfunction "1_1") (pintype "passive"))
      (node (ref "SW8") (pin "3") (pintype "passive"))
    )
    (net (code "54") (name "GND") (class "Default")
      (node (ref "C24") (pin "2") (pinfunction "2_2") (pintype "passive"))
      (node (ref "C47") (pin "2") (pinfunction "2_2") (pintype "passive"))
      (node (ref "C75") (pin "2") (pinfunction "2_2") (pintype "passive"))
      (node (ref "C76") (pin "2") (pinfunction "2_2") (pintype "passive"))
      (node (ref "C77") (pin "2") (pinfunction "2_2") (pintype "passive"))
      (node (ref "C8") (pin "2") (pinfunction "2_2") (pintype "passive"))
      (node (ref "C9") (pin "2") (pinfunction "2_2") (pintype "passive"))
      (node (ref "D1") (pin "2") (pintype "passive"))
      (node (ref "D15") (pin "2") (pintype "passive"))
      (node (ref "D21") (pin "2") (pintype "passive"))
      (node (ref "D22") (pin "2") (pintype "passive"))
      (node (ref "R127") (pin "2") (pinfunction "2_2") (pintype "passive"))
      (node (ref "R129") (pin "2") (pinfunction "2_2") (pintype "passive"))
      (node (ref "R15") (pin "1") (pinfunction "1_1") (pintype "passive"))
      (node (ref "R212") (pin "2") (pinfunction "2_2") (pintype "passive"))
      (node (ref "R213") (pin "2") (pinfunction "2_2") (pintype "passive"))
      (node (ref "R214") (pin "2") (pinfunction "2_2") (pintype "passive"))
      (node (ref "R215") (pin "2") (pinfunction "2_2") (pintype "passive"))
      (node (ref "R27") (pin "2") (pinfunction "2_2") (pintype "passive"))
      (node (ref "R289") (pin "1") (pinfunction "1_1") (pintype "passive"))
      (node (ref "R29") (pin "2") (pinfunction "2_2") (pintype "passive"))
      (node (ref "R30") (pin "2") (pinfunction "2_2") (pintype "passive"))
      (node (ref "R31") (pin "2") (pinfunction "2_2") (pintype "passive"))
      (node (ref "R80") (pin "1") (pinfunction "1_1") (pintype "passive"))
      (node (ref "SW1") (pin "3") (pinfunction "T3_3") (pintype "passive"))
      (node (ref "SW2") (pin "3") (pinfunction "T3_3") (pintype "passive"))
      (node (ref "SW3") (pin "5") (pintype "passive"))
      (node (ref "SW3") (pin "6") (pintype "passive"))
      (node (ref "SW3") (pin "7") (pintype "passive"))
      (node (ref "SW3") (pin "8") (pintype "passive"))
      (node (ref "SW5") (pin "3") (pinfunction "T3_3") (pintype "passive"))
      (node (ref "SW5") (pin "4") (pinfunction "T3_4") (pintype "passive"))
      (node (ref "SW7") (pin "3") (pinfunction "T3_3") (pintype "passive"))
      (node (ref "SW7") (pin "4") (pinfunction "T3_4") (pintype "passive"))
      (node (ref "U2") (pin "4") (pinfunction "GND_4") (pintype "power_in"))
      (node (ref "U3") (pin "2") (pinfunction "GND_2") (pintype "power_in"))
      (node (ref "U4") (pin "2") (pinfunction "GND_2") (pintype "power_in"))
      (node (ref "U7") (pin "2") (pinfunction "GND_2") (pintype "power_in"))
    )
    (net (code "55") (name "MLINK_3V3") (class "Default")
      (node (ref "D19") (pin "2") (pinfunction "A_2") (pintype "passive"))
    )
    (net (code "56") (name "Net-(D4-C)") (class "Default")
      (node (ref "D4") (pin "1") (pinfunction "C_1") (pintype "passive"))
      (node (ref "R76") (pin "2") (pinfunction "2_2") (pintype "passive"))
    )
    (net (code "57") (name "Net-(D5-C)") (class "Default")
      (node (ref "D5") (pin "1") (pinfunction "C_1") (pintype "passive"))
      (node (ref "R93") (pin "2") (pinfunction "2_2") (pintype "passive"))
    )
    (net (code "58") (name "Net-(D6-C)") (class "Default")
      (node (ref "D6") (pin "1") (pinfunction "C_1") (pintype "passive"))
      (node (ref "R74") (pin "2") (pinfunction "2_2") (pintype "passive"))
    )
    (net (code "59") (name "Net-(D7-C)") (class "Default")
      (node (ref "D7") (pin "1") (pinfunction "C_1") (pintype "passive"))
      (node (ref "R75") (pin "2") (pinfunction "2_2") (pintype "passive"))
    )
    (net (code "60") (name "Net-(D8-C)") (class "Default")
      (node (ref "D8") (pin "1") (pinfunction "C_1") (pintype "passive"))
      (node (ref "R72") (pin "2") (pinfunction "2_2") (pintype "passive"))
    )
    (net (code "61") (name "Net-(D9-C)") (class "Default")
      (node (ref "D9") (pin "1") (pinfunction "C_1") (pintype "passive"))
      (node (ref "R73") (pin "2") (pinfunction "2_2") (pintype "passive"))
    )
    (net (code "62") (name "Net-(D10-C)") (class "Default")
      (node (ref "D10") (pin "1") (pinfunction "C_1") (pintype "passive"))
      (node (ref "R80") (pin "2") (pinfunction "2_2") (pintype "passive"))
    )
    (net (code "63") (name "Net-(D19-C)") (class "Default")
      (node (ref "D19") (pin "1") (pinfunction "C_1") (pintype "passive"))
      (node (ref "R289") (pin "2") (pinfunction "2_2") (pintype "passive"))
    )
    (net (code "64") (name "Net-(R27-Pad1)") (class "Default")
      (node (ref "R27") (pin "1") (pinfunction "1_1") (pintype "passive"))
      (node (ref "SW8") (pin "8") (pintype "passive"))
    )
    (net (code "65") (name "Net-(R29-Pad1)") (class "Default")
      (node (ref "R29") (pin "1") (pinfunction "1_1") (pintype "passive"))
      (node (ref "SW8") (pin "7") (pintype "passive"))
    )
    (net (code "66") (name "Net-(R30-Pad1)") (class "Default")
      (node (ref "R30") (pin "1") (pinfunction "1_1") (pintype "passive"))
      (node (ref "SW8") (pin "6") (pintype "passive"))
    )
    (net (code "67") (name "Net-(R31-Pad1)") (class "Default")
      (node (ref "R31") (pin "1") (pinfunction "1_1") (pintype "passive"))
      (node (ref "SW8") (pin "5") (pintype "passive"))
    )
    (net (code "68") (name "Net-(R103-Pad2)") (class "Default")
      (node (ref "R103") (pin "2") (pinfunction "2_2") (pintype "passive"))
      (node (ref "R215") (pin "1") (pinfunction "1_1") (pintype "passive"))
      (node (ref "R218") (pin "1") (pinfunction "1_1") (pintype "passive"))
      (node (ref "SW3") (pin "4") (pintype "passive"))
    )
    (net (code "69") (name "Net-(R125-Pad1)") (class "Default")
      (node (ref "R125") (pin "1") (pinfunction "1_1") (pintype "passive"))
      (node (ref "R127") (pin "1") (pinfunction "1_1") (pintype "passive"))
      (node (ref "SW1") (pin "4") (pinfunction "T3_4") (pintype "passive"))
    )
    (net (code "70") (name "Net-(R128-Pad1)") (class "Default")
      (node (ref "R128") (pin "1") (pinfunction "1_1") (pintype "passive"))
      (node (ref "R129") (pin "1") (pinfunction "1_1") (pintype "passive"))
      (node (ref "SW2") (pin "4") (pinfunction "T3_4") (pintype "passive"))
    )
    (net (code "71") (name "Net-(R212-Pad1)") (class "Default")
      (node (ref "R212") (pin "1") (pinfunction "1_1") (pintype "passive"))
      (node (ref "R94") (pin "2") (pinfunction "2_2") (pintype "passive"))
      (node (ref "SW3") (pin "2") (pintype "passive"))
    )
    (net (code "72") (name "Net-(R213-Pad1)") (class "Default")
      (node (ref "R213") (pin "1") (pinfunction "1_1") (pintype "passive"))
      (node (ref "R82") (pin "2") (pinfunction "2_2") (pintype "passive"))
      (node (ref "SW3") (pin "1") (pintype "passive"))
    )
    (net (code "73") (name "Net-(R214-Pad1)") (class "Default")
      (node (ref "R214") (pin "1") (pinfunction "1_1") (pintype "passive"))
      (node (ref "R216") (pin "1") (pinfunction "1_1") (pintype "passive"))
      (node (ref "R99") (pin "2") (pinfunction "2_2") (pintype "passive"))
      (node (ref "SW3") (pin "3") (pintype "passive"))
    )
    (net (code "74") (name "Net-(RGB1-B)") (class "Default")
      (node (ref "R79") (pin "2") (pinfunction "2_2") (pintype "passive"))
      (node (ref "RGB1") (pin "3") (pinfunction "B_3") (pintype "passive"))
    )
    (net (code "75") (name "Net-(RGB1-G)") (class "Default")
      (node (ref "R78") (pin "2") (pinfunction "2_2") (pintype "passive"))
      (node (ref "RGB1") (pin "2") (pinfunction "G_2") (pintype "passive"))
    )
    (net (code "76") (name "Net-(RGB1-R)") (class "Default")
      (node (ref "R77") (pin "2") (pinfunction "2_2") (pintype "passive"))
      (node (ref "RGB1") (pin "1") (pinfunction "R_1") (pintype "passive"))
    )
    (net (code "77") (name "Net-(U3-1Y)") (class "Default")
      (node (ref "R72") (pin "1") (pinfunction "1_1") (pintype "passive"))
      (node (ref "U3") (pin "6") (pinfunction "1Y_6") (pintype "output"))
    )
    (net (code "78") (name "Net-(U3-2Y)") (class "Default")
      (node (ref "R73") (pin "1") (pinfunction "1_1") (pintype "passive"))
      (node (ref "U3") (pin "4") (pinfunction "2Y_4") (pintype "output"))
    )
    (net (code "79") (name "Net-(U4-1Y)") (class "Default")
      (node (ref "R74") (pin "1") (pinfunction "1_1") (pintype "passive"))
      (node (ref "U4") (pin "6") (pinfunction "1Y_6") (pintype "output"))
    )
    (net (code "80") (name "Net-(U4-2Y)") (class "Default")
      (node (ref "R75") (pin "1") (pinfunction "1_1") (pintype "passive"))
      (node (ref "U4") (pin "4") (pinfunction "2Y_4") (pintype "output"))
    )
    (net (code "81") (name "Net-(U7-1Y)") (class "Default")
      (node (ref "R76") (pin "1") (pinfunction "1_1") (pintype "passive"))
      (node (ref "U7") (pin "6") (pinfunction "1Y_6") (pintype "output"))
    )
    (net (code "82") (name "Net-(U7-2Y)") (class "Default")
      (node (ref "R93") (pin "1") (pinfunction "1_1") (pintype "passive"))
      (node (ref "U7") (pin "4") (pinfunction "2Y_4") (pintype "output"))
    )
  )
)
